# Wi_Drive_Power.net
KiCad netlist of a schematic drawn in Altium Designer
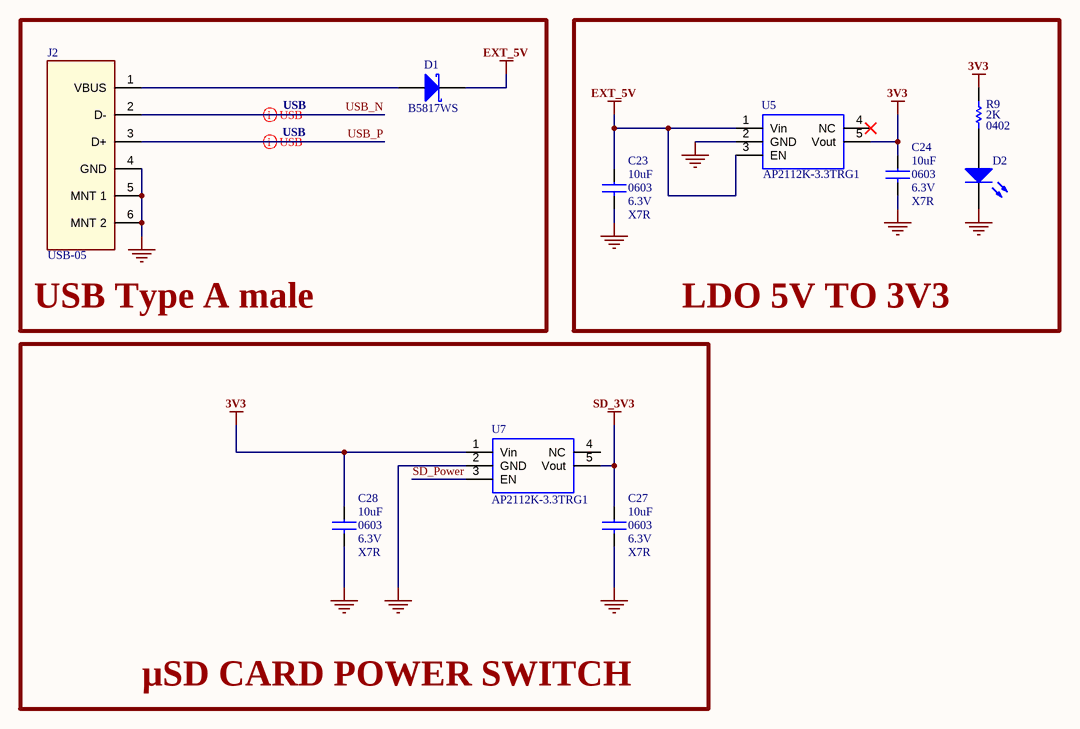
[diagram p0: Wi_Drive Power.SchDoc]

(export (version "E")
  (design (tool "Eeschema 10.0.6"))
  (components
    (comp (ref "C23")
      (value "10uF")
      (footprint "CAPC0603")
      (description "CAP CER 10uF 6.3V X7R 0603")
      (fields
        (field (name "VOLTAGE") "6.3V")
        (field (name "DIELECTRIC") "X7R")
        (field (name "CASE/PACKAGE") "0603")
      )
      (libsource (lib "CUSTOM SCH") (part "Cap"))
    )
    (comp (ref "C24")
      (value "10uF")
      (footprint "CAPC0603")
      (description "CAP CER 10uF 6.3V X7R 0603")
      (fields
        (field (name "VOLTAGE") "6.3V")
        (field (name "DIELECTRIC") "X7R")
        (field (name "CASE/PACKAGE") "0603")
      )
      (libsource (lib "CUSTOM SCH") (part "Cap"))
    )
    (comp (ref "C27")
      (value "10uF")
      (footprint "CAPC0603")
      (description "CAP CER 10uF 6.3V X7R 0603")
      (fields
        (field (name "VOLTAGE") "6.3V")
        (field (name "DIELECTRIC") "X7R")
        (field (name "CASE/PACKAGE") "0603")
      )
      (libsource (lib "CUSTOM SCH") (part "Cap"))
    )
    (comp (ref "C28")
      (value "10uF")
      (footprint "CAPC0603")
      (description "CAP CER 10uF 6.3V X7R 0603")
      (fields
        (field (name "VOLTAGE") "6.3V")
        (field (name "DIELECTRIC") "X7R")
        (field (name "CASE/PACKAGE") "0603")
      )
      (libsource (lib "CUSTOM SCH") (part "Cap"))
    )
    (comp (ref "D1")
      (value "~")
      (footprint "SOD-323")
      (description "20V 1A 450mV @ 1A SOD-323 Schottky Barrier Diodes (SBD) RoHS")
      (fields (field (name "MANUFACTURER PART NUMBER") "B5817WS"))
      (libsource (lib "Pd's Sch Lib") (part "B5817WS"))
    )
    (comp (ref "D2")
      (value "~")
      (footprint "LED_0603")
      (description "LED, RED,SMD, 0603")
      (libsource (lib "Miscellaneous Devices") (part "LED1"))
    )
    (comp (ref "J2")
      (value "~")
      (footprint "Molex_48037-0001_0")
      (description "USB A-type Plug Male PCB R/A")
      (fields (field (name "MANUFACTURER PART NUMBER") "USB-05"))
      (libsource (lib "CUSTOM TNY290PG") (part "USB MALE"))
    )
    (comp (ref "R9")
      (value "2K")
      (footprint "RESC0402")
      (description "Thick Film Resistor -  2Kohm, 1%, 0402")
      (fields (field (name "CASE/PACKAGE") "0402"))
      (libsource (lib "Pd's Sch Lib") (part "Resistor"))
    )
    (comp (ref "U5")
      (value "~")
      (footprint "SOT25")
      (description "LDO Voltage Regulators 600mA CMOS LDO 50mA 3.3V 250mV")
      (fields (field (name "MANUFACTURER PART NUMBER") "AP2112K-3.3TRG1"))
      (libsource (lib "VEGG_Schlib") (part "LDO_5V_3V"))
    )
    (comp (ref "U7")
      (value "~")
      (footprint "SOT25")
      (description "LDO Voltage Regulators 600mA CMOS LDO 50mA 3.3V 250mV")
      (fields (field (name "MANUFACTURER PART NUMBER") "AP2112K-3.3TRG1"))
      (libsource (lib "VEGG_Schlib") (part "LDO_5V_3V"))
    )
  )
  (nets
    (net (code "1") (name "/SD_Power") (class "Default")
      (node (ref "U7") (pin "3") (pinfunction "EN_3") (pintype "passive"))
    )
    (net (code "2") (name "/USB_N") (class "Default")
      (node (ref "J2") (pin "2") (pinfunction "D-_2") (pintype "passive"))
    )
    (net (code "3") (name "/USB_P") (class "Default")
      (node (ref "J2") (pin "3") (pinfunction "D+_3") (pintype "passive"))
    )
    (net (code "4") (name "3V3") (class "Default")
      (node (ref "C24") (pin "1") (pinfunction "1_1") (pintype "passive"))
      (node (ref "C28") (pin "1") (pinfunction "1_1") (pintype "passive"))
      (node (ref "R9") (pin "1") (pinfunction "1_1") (pintype "passive"))
      (node (ref "U5") (pin "5") (pinfunction "Vout_5") (pintype "power_in"))
      (node (ref "U7") (pin "1") (pinfunction "Vin_1") (pintype "power_in"))
    )
    (net (code "5") (name "EXT_5V") (class "Default")
      (node (ref "C23") (pin "1") (pinfunction "1_1") (pintype "passive"))
      (node (ref "D1") (pin "K") (pinfunction "K_K") (pintype "passive"))
      (node (ref "U5") (pin "1") (pinfunction "Vin_1") (pintype "power_in"))
      (node (ref "U5") (pin "3") (pinfunction "EN_3") (pintype "passive"))
    )
    (net (code "6") (name "GND") (class "Default")
      (node (ref "C23") (pin "2") (pinfunction "2_2") (pintype "passive"))
      (node (ref "C24") (pin "2") (pinfunction "2_2") (pintype "passive"))
      (node (ref "C27") (pin "2") (pinfunction "2_2") (pintype "passive"))
      (node (ref "C28") (pin "2") (pinfunction "2_2") (pintype "passive"))
      (node (ref "D2") (pin "K") (pinfunction "K_K") (pintype "passive"))
      (node (ref "J2") (pin "4") (pinfunction "GND_4") (pintype "passive"))
      (node (ref "J2") (pin "5") (pinfunction "MNT_1_5") (pintype "passive"))
      (node (ref "J2") (pin "6") (pinfunction "MNT_2_6") (pintype "passive"))
      (node (ref "U5") (pin "2") (pinfunction "GND_2") (pintype "power_in"))
      (node (ref "U7") (pin "2") (pinfunction "GND_2") (pintype "power_in"))
    )
    (net (code "7") (name "Net-(D2-PadA)") (class "Default")
      (node (ref "D2") (pin "A") (pinfunction "A_A") (pintype "passive"))
      (node (ref "R9") (pin "2") (pinfunction "2_2") (pintype "passive"))
    )
    (net (code "8") (name "Net-(J2-VBUS)") (class "Default")
      (node (ref "D1") (pin "A") (pinfunction "A_A") (pintype "passive"))
      (node (ref "J2") (pin "1") (pinfunction "VBUS_1") (pintype "passive"))
    )
    (net (code "9") (name "SD_3V3") (class "Default")
      (node (ref "C27") (pin "1") (pinfunction "1_1") (pintype "passive"))
      (node (ref "U7") (pin "5") (pinfunction "Vout_5") (pintype "power_in"))
    )
    (net (code "10") (name "unconnected-(U5-NC-Pad4)") (class "Default")
      (node (ref "U5") (pin "4") (pinfunction "NC_4") (pintype "passive+no_connect"))
    )
    (net (code "11") (name "unconnected-(U7-NC-Pad4)") (class "Default")
      (node (ref "U7") (pin "4") (pinfunction "NC_4") (pintype "passive"))
    )
  )
)
